# bare.net
KiCad netlist of a schematic drawn in EAGLE
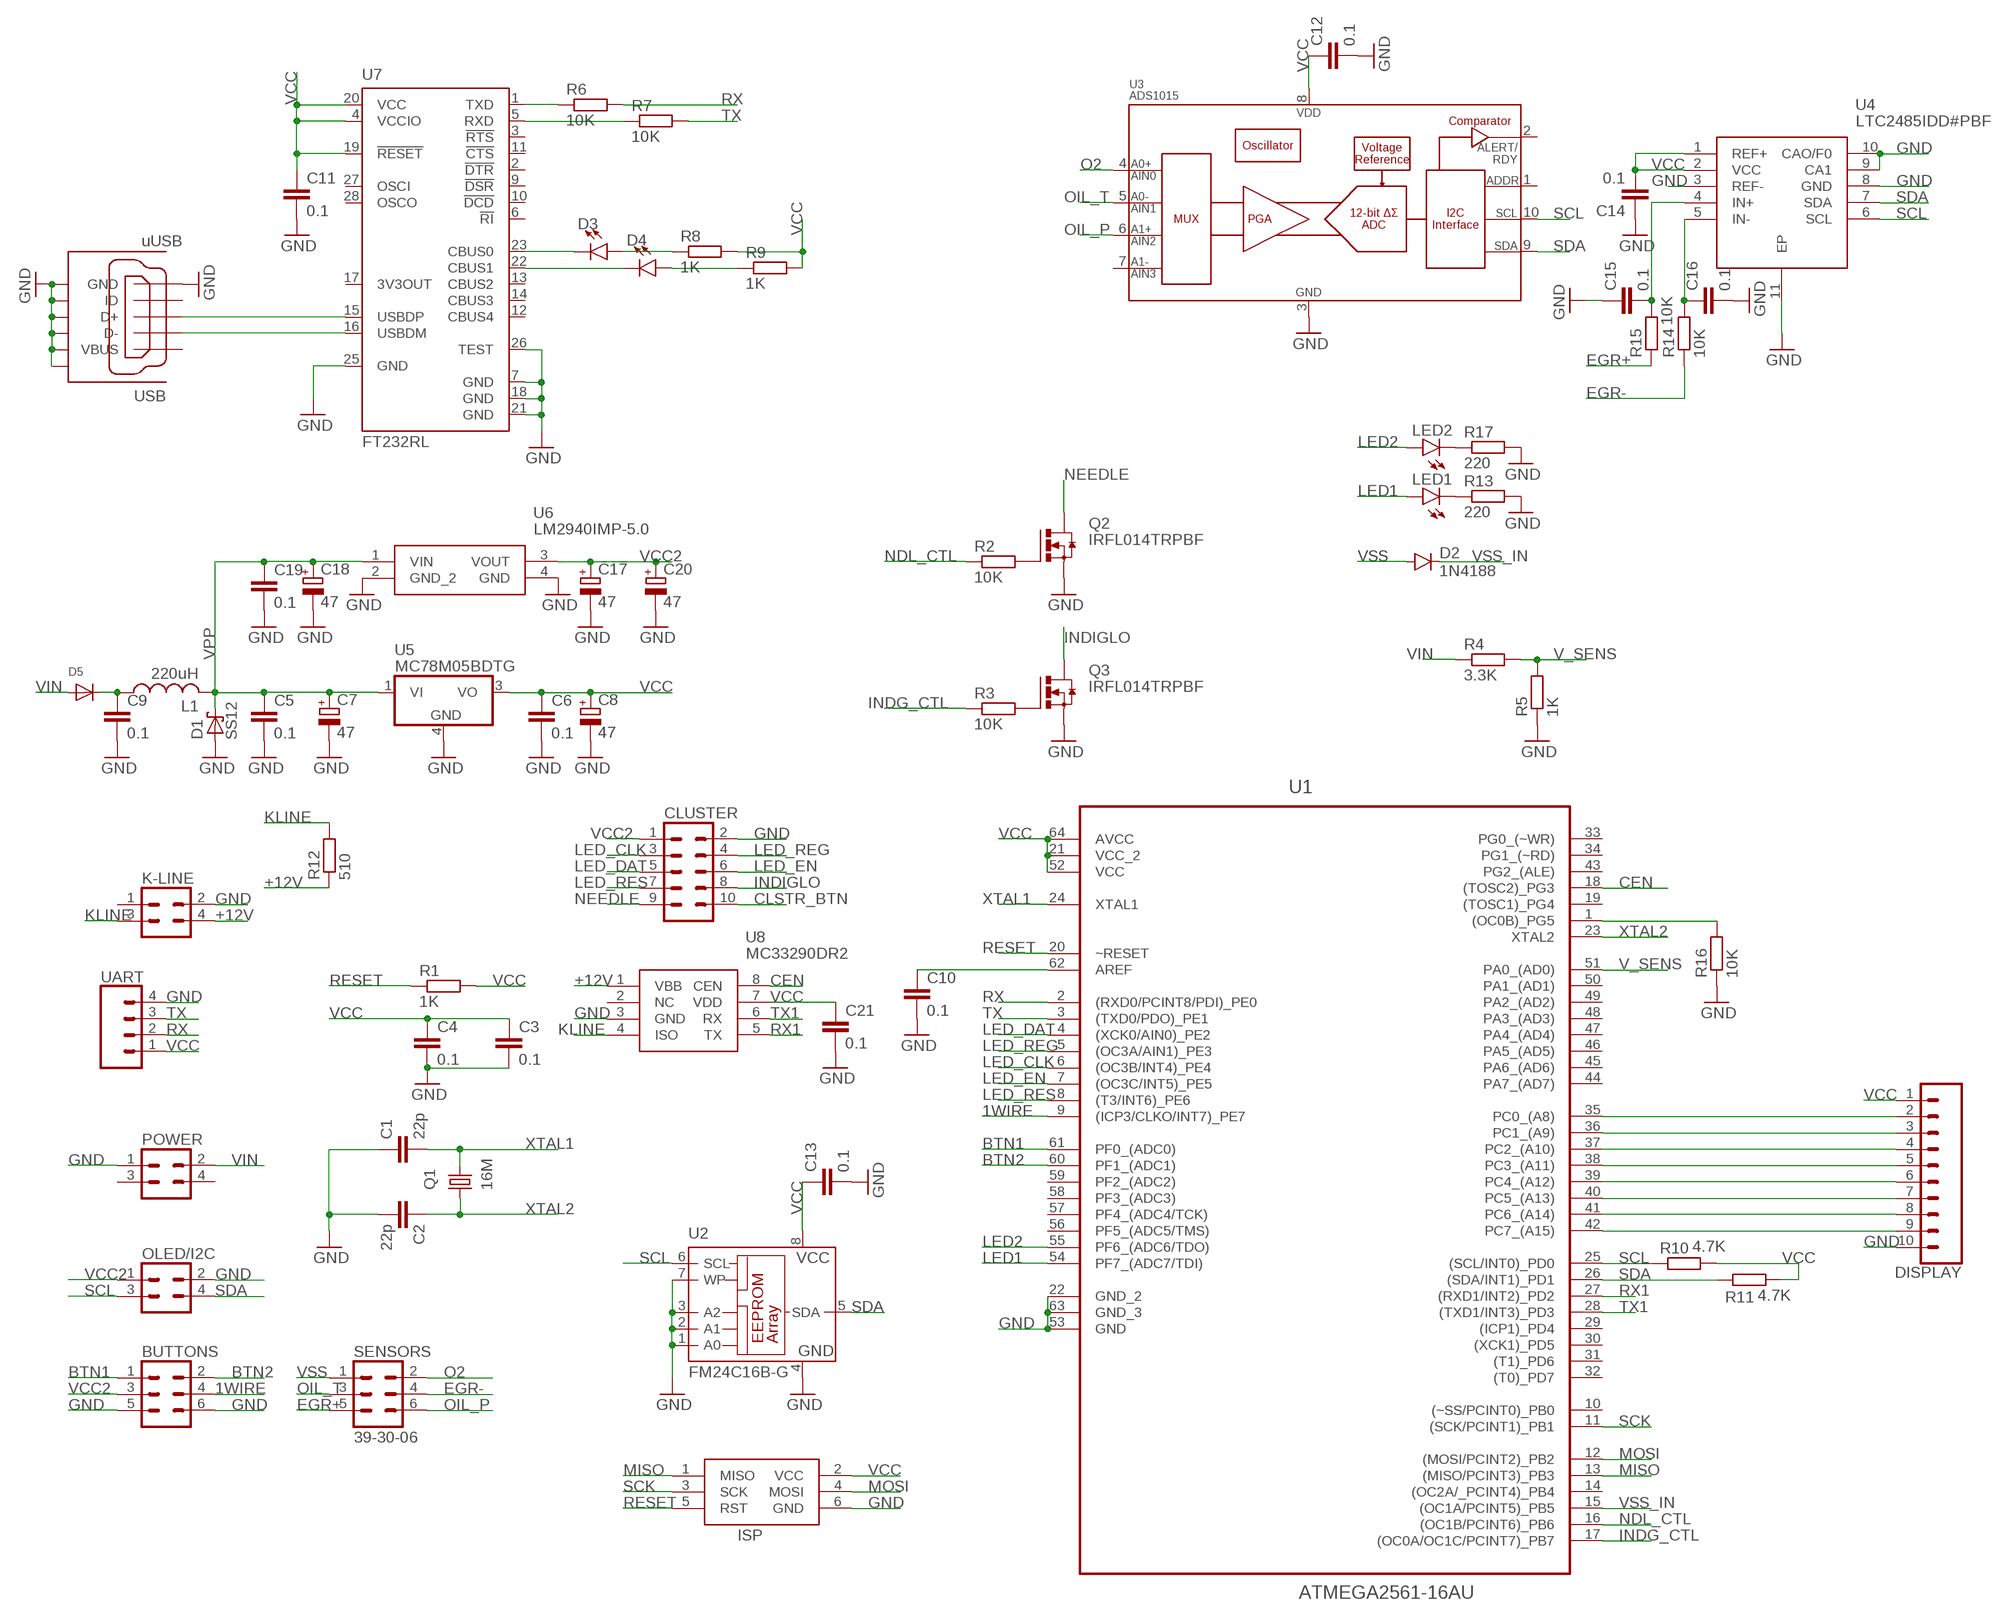
[diagram p0: schematic, sheet 1]

(export (version "E")
  (design (tool "Eeschema 10.0.6"))
  (components
    (comp (ref "BUTTONS")
      (value "39-30-06")
      (footprint "eagle-import:39-30-_06_")
      (libsource (lib "eagle-import") (part "39-30-?06?"))
    )
    (comp (ref "C1")
      (value "22p")
      (footprint "eagle-import:C0603K")
      (libsource (lib "eagle-import") (part "C-EUC0603K"))
    )
    (comp (ref "C2")
      (value "22p")
      (footprint "eagle-import:C0603K")
      (libsource (lib "eagle-import") (part "C-EUC0603K"))
    )
    (comp (ref "C3")
      (value "0.1")
      (footprint "eagle-import:C0603K")
      (libsource (lib "eagle-import") (part "C-EUC0603K"))
    )
    (comp (ref "C4")
      (value "0.1")
      (footprint "eagle-import:C0603K")
      (libsource (lib "eagle-import") (part "C-EUC0603K"))
    )
    (comp (ref "C5")
      (value "0.1")
      (footprint "eagle-import:C0805K")
      (libsource (lib "eagle-import") (part "C-EUC0805K"))
    )
    (comp (ref "C6")
      (value "0.1")
      (footprint "eagle-import:C0805K")
      (libsource (lib "eagle-import") (part "C-EUC0805K"))
    )
    (comp (ref "C7")
      (value "47")
      (footprint "eagle-import:SMC_C")
      (libsource (lib "eagle-import") (part "CPOL-EUSMCC"))
    )
    (comp (ref "C8")
      (value "47")
      (footprint "eagle-import:SMC_C")
      (libsource (lib "eagle-import") (part "CPOL-EUSMCC"))
    )
    (comp (ref "C9")
      (value "0.1")
      (footprint "eagle-import:C0805K")
      (libsource (lib "eagle-import") (part "C-EUC0805K"))
    )
    (comp (ref "C10")
      (value "0.1")
      (footprint "eagle-import:C0603K")
      (libsource (lib "eagle-import") (part "C-EUC0603K"))
    )
    (comp (ref "C11")
      (value "0.1")
      (footprint "eagle-import:C0603K")
      (libsource (lib "eagle-import") (part "C-EUC0603K"))
    )
    (comp (ref "C12")
      (value "0.1")
      (footprint "eagle-import:C0805K")
      (libsource (lib "eagle-import") (part "C-EUC0805K"))
    )
    (comp (ref "C13")
      (value "0.1")
      (footprint "eagle-import:C0603K")
      (libsource (lib "eagle-import") (part "C-EUC0603K"))
    )
    (comp (ref "C14")
      (value "0.1")
      (footprint "eagle-import:C0603K")
      (libsource (lib "eagle-import") (part "C-EUC0603K"))
    )
    (comp (ref "C15")
      (value "0.1")
      (footprint "eagle-import:C0603K")
      (libsource (lib "eagle-import") (part "C-EUC0603K"))
    )
    (comp (ref "C16")
      (value "0.1")
      (footprint "eagle-import:C0603K")
      (libsource (lib "eagle-import") (part "C-EUC0603K"))
    )
    (comp (ref "C17")
      (value "47")
      (footprint "eagle-import:SMC_C")
      (libsource (lib "eagle-import") (part "CPOL-EUSMCC"))
    )
    (comp (ref "C18")
      (value "47")
      (footprint "eagle-import:SMC_C")
      (libsource (lib "eagle-import") (part "CPOL-EUSMCC"))
    )
    (comp (ref "C19")
      (value "0.1")
      (footprint "eagle-import:C0805K")
      (libsource (lib "eagle-import") (part "C-EUC0805K"))
    )
    (comp (ref "C20")
      (value "47")
      (footprint "eagle-import:SMC_C")
      (libsource (lib "eagle-import") (part "CPOL-EUSMCC"))
    )
    (comp (ref "C21")
      (value "0.1")
      (footprint "eagle-import:C0603K")
      (libsource (lib "eagle-import") (part "C-EUC0603K"))
    )
    (comp (ref "CLUSTER")
      (value "39-30-10")
      (footprint "eagle-import:39-30-_10_")
      (libsource (lib "eagle-import") (part "39-30-?10?"))
    )
    (comp (ref "D1")
      (value "SS12")
      (footprint "eagle-import:SOD80C")
      (libsource (lib "eagle-import") (part "BAS85"))
    )
    (comp (ref "D2")
      (value "1N4188")
      (footprint "eagle-import:SOD-323")
      (libsource (lib "eagle-import") (part "DIODESOD"))
    )
    (comp (ref "D3")
      (value "GREEN")
      (footprint "eagle-import:LED-0603")
      (libsource (lib "eagle-import") (part "LED-GREEN0603"))
    )
    (comp (ref "D4")
      (value "RED")
      (footprint "eagle-import:LED-0603")
      (libsource (lib "eagle-import") (part "LED-RED0603"))
    )
    (comp (ref "D5")
      (value "DIODESMA")
      (footprint "eagle-import:SMADIODE")
      (libsource (lib "eagle-import") (part "adafruit_420_DIODESMA"))
    )
    (comp (ref "DISPLAY")
      (value "CONN_10\"")
      (footprint "eagle-import:1X10")
      (libsource (lib "eagle-import") (part "CONN_10{dblquote}"))
    )
    (comp (ref "ISP")
      (value "AVRISP-6")
      (footprint "eagle-import:AVRISP")
      (libsource (lib "eagle-import") (part "AVRISP-6"))
    )
    (comp (ref "K-LINE")
      (value "39-30-04")
      (footprint "eagle-import:39-30-_04_")
      (libsource (lib "eagle-import") (part "39-30-?04?"))
    )
    (comp (ref "L1")
      (value "220uH")
      (footprint "eagle-import:PIS2816")
      (libsource (lib "eagle-import") (part "L-USPIS2816"))
    )
    (comp (ref "LED1")
      (value "LEDCHIP-LED0805")
      (footprint "eagle-import:CHIP-LED0805")
      (libsource (lib "eagle-import") (part "LEDCHIP-LED0805"))
    )
    (comp (ref "LED2")
      (value "LEDCHIP-LED0805")
      (footprint "eagle-import:CHIP-LED0805")
      (libsource (lib "eagle-import") (part "LEDCHIP-LED0805"))
    )
    (comp (ref "OLED/I2C")
      (value "39-30-04")
      (footprint "eagle-import:39-30-_04_")
      (libsource (lib "eagle-import") (part "39-30-?04?"))
    )
    (comp (ref "POWER")
      (value "39-30-04")
      (footprint "eagle-import:39-30-_04_")
      (libsource (lib "eagle-import") (part "39-30-?04?"))
    )
    (comp (ref "Q1")
      (value "16M")
      (footprint "eagle-import:3.2X2.5_KX-7")
      (libsource (lib "eagle-import") (part "KX-7"))
    )
    (comp (ref "Q2")
      (value "IRFL014TRPBF")
      (footprint "eagle-import:SOT223")
      (libsource (lib "eagle-import") (part "N-HEXFET-2D_?-SOT232"))
    )
    (comp (ref "Q3")
      (value "IRFL014TRPBF")
      (footprint "eagle-import:SOT223")
      (libsource (lib "eagle-import") (part "N-HEXFET-2D_?-SOT232"))
    )
    (comp (ref "R1")
      (value "1K")
      (footprint "eagle-import:R0603")
      (libsource (lib "eagle-import") (part "R-EU_R0603"))
    )
    (comp (ref "R2")
      (value "10K")
      (footprint "eagle-import:R0603")
      (libsource (lib "eagle-import") (part "R-EU_R0603"))
    )
    (comp (ref "R3")
      (value "10K")
      (footprint "eagle-import:R0603")
      (libsource (lib "eagle-import") (part "R-EU_R0603"))
    )
    (comp (ref "R4")
      (value "3.3K")
      (footprint "eagle-import:R0603")
      (libsource (lib "eagle-import") (part "R-EU_R0603"))
    )
    (comp (ref "R5")
      (value "1K")
      (footprint "eagle-import:R0603")
      (libsource (lib "eagle-import") (part "R-EU_R0603"))
    )
    (comp (ref "R6")
      (value "10K")
      (footprint "eagle-import:R0603")
      (libsource (lib "eagle-import") (part "R-EU_R0603"))
    )
    (comp (ref "R7")
      (value "10K")
      (footprint "eagle-import:R0603")
      (libsource (lib "eagle-import") (part "R-EU_R0603"))
    )
    (comp (ref "R8")
      (value "1K")
      (footprint "eagle-import:R0603")
      (libsource (lib "eagle-import") (part "R-EU_R0603"))
    )
    (comp (ref "R9")
      (value "1K")
      (footprint "eagle-import:R0603")
      (libsource (lib "eagle-import") (part "R-EU_R0603"))
    )
    (comp (ref "R10")
      (value "4.7K")
      (footprint "eagle-import:R0603")
      (libsource (lib "eagle-import") (part "R-EU_R0603"))
    )
    (comp (ref "R11")
      (value "4.7K")
      (footprint "eagle-import:R0603")
      (libsource (lib "eagle-import") (part "R-EU_R0603"))
    )
    (comp (ref "R12")
      (value "510")
      (footprint "eagle-import:R0603")
      (libsource (lib "eagle-import") (part "R-EU_R0603"))
    )
    (comp (ref "R13")
      (value "220")
      (footprint "eagle-import:R0603")
      (libsource (lib "eagle-import") (part "R-EU_R0603"))
    )
    (comp (ref "R14")
      (value "10K")
      (footprint "eagle-import:R0603")
      (libsource (lib "eagle-import") (part "R-EU_R0603"))
    )
    (comp (ref "R15")
      (value "10K")
      (footprint "eagle-import:R0603")
      (libsource (lib "eagle-import") (part "R-EU_R0603"))
    )
    (comp (ref "R16")
      (value "10K")
      (footprint "eagle-import:R0603")
      (libsource (lib "eagle-import") (part "R-EU_R0603"))
    )
    (comp (ref "R17")
      (value "220")
      (footprint "eagle-import:R0603")
      (libsource (lib "eagle-import") (part "R-EU_R0603"))
    )
    (comp (ref "SENSORS")
      (value "39-30-06")
      (footprint "eagle-import:39-30-_06_")
      (libsource (lib "eagle-import") (part "39-30-?06?"))
    )
    (comp (ref "U1")
      (value "ATMEGA2561-16AU")
      (footprint "eagle-import:QFP80P1600X1600X120-64N")
      (libsource (lib "eagle-import") (part "ATMEGA2561-16AU"))
    )
    (comp (ref "U2")
      (value "FM24C16B-G")
      (footprint "eagle-import:SO-08")
      (fields (field (name "MPN") "24AA256T-I/SM"))
      (libsource (lib "eagle-import") (part "24SNAA256"))
    )
    (comp (ref "U3")
      (value "ADS1015")
      (footprint "eagle-import:MSOP10")
      (libsource (lib "eagle-import") (part "ADS1015"))
    )
    (comp (ref "U4")
      (value "LTC2485IDD#PBF")
      (footprint "eagle-import:SON50P300X300X80-11N")
      (fields (field (name "RS_PART_NUMBER") "1580322"))
      (libsource (lib "eagle-import") (part "LTC2485IDD#PBF"))
    )
    (comp (ref "U5")
      (value "MC78M05BDTG")
      (footprint "eagle-import:DPACK_3")
      (libsource (lib "eagle-import") (part "MC78M05BDTG"))
    )
    (comp (ref "U6")
      (value "LM2940IMP-5.0")
      (footprint "eagle-import:SOT230P696X180-4N")
      (fields (field (name "MOUSER_PART_NUMBER") "926-LM2940IMP-50"))
      (libsource (lib "eagle-import") (part "LM2940IMP-5.0"))
    )
    (comp (ref "U7")
      (value "FT232RL")
      (footprint "eagle-import:SSOP28")
      (libsource (lib "eagle-import") (part "FT232RL"))
    )
    (comp (ref "U8")
      (value "MC33290DR2")
      (footprint "eagle-import:SOIC127P600X175-8N")
      (libsource (lib "eagle-import") (part "MC33290DR2"))
    )
    (comp (ref "UART")
      (value "UART")
      (footprint "eagle-import:1X04")
      (libsource (lib "eagle-import") (part "CONN_04"))
    )
    (comp (ref "USB")
      (value "uUSB")
      (footprint "eagle-import:GHI-CONNECTORS_10118192-0001LF(MICRO-USB-B-AMPHENOL-FCI)")
      (libsource (lib "eagle-import") (part "GHI-CONNECTORS_10118192-0001LF"))
    )
  )
  (nets
    (net (code "1") (name "/+12V") (class "Default")
      (node (ref "K-LINE") (pin "4") (pinfunction "4_4") (pintype "passive"))
      (node (ref "R12") (pin "1") (pinfunction "1_1") (pintype "passive"))
      (node (ref "U8") (pin "1") (pinfunction "VBB_1") (pintype "bidirectional"))
    )
    (net (code "2") (name "/1WIRE") (class "Default")
      (node (ref "BUTTONS") (pin "4") (pinfunction "4_4") (pintype "passive"))
      (node (ref "U1") (pin "9") (pinfunction "(ICP3/CLKO/INT7)_PE7_9") (pintype "bidirectional"))
    )
    (net (code "3") (name "/BTN1") (class "Default")
      (node (ref "BUTTONS") (pin "1") (pinfunction "1_1") (pintype "passive"))
      (node (ref "U1") (pin "61") (pinfunction "PF0_(ADC0)_61") (pintype "bidirectional"))
    )
    (net (code "4") (name "/BTN2") (class "Default")
      (node (ref "BUTTONS") (pin "2") (pinfunction "2_2") (pintype "passive"))
      (node (ref "U1") (pin "60") (pinfunction "PF1_(ADC1)_60") (pintype "bidirectional"))
    )
    (net (code "5") (name "/CEN") (class "Default")
      (node (ref "U1") (pin "18") (pinfunction "(TOSC2)_PG3_18") (pintype "bidirectional"))
      (node (ref "U8") (pin "8") (pinfunction "CEN_8") (pintype "bidirectional"))
    )
    (net (code "6") (name "/CLSTR_BTN") (class "Default")
      (node (ref "CLUSTER") (pin "10") (pinfunction "10_10") (pintype "passive"))
      (node (ref "R16") (pin "2") (pinfunction "2_2") (pintype "passive"))
      (node (ref "U1") (pin "1") (pinfunction "(OC0B)_PG5_1") (pintype "bidirectional"))
    )
    (net (code "7") (name "/EGR+") (class "Default")
      (node (ref "R15") (pin "1") (pinfunction "1_1") (pintype "passive"))
      (node (ref "SENSORS") (pin "5") (pinfunction "5_5") (pintype "passive"))
    )
    (net (code "8") (name "/EGR-") (class "Default")
      (node (ref "R14") (pin "1") (pinfunction "1_1") (pintype "passive"))
      (node (ref "SENSORS") (pin "4") (pinfunction "4_4") (pintype "passive"))
    )
    (net (code "9") (name "/INDG_CTL") (class "Default")
      (node (ref "R3") (pin "1") (pinfunction "1_1") (pintype "passive"))
      (node (ref "U1") (pin "17") (pinfunction "(OC0A/OC1C/PCINT7)_PB7_17") (pintype "bidirectional"))
    )
    (net (code "10") (name "/INDIGLO") (class "Default")
      (node (ref "CLUSTER") (pin "8") (pinfunction "8_8") (pintype "passive"))
      (node (ref "Q3") (pin "2") (pinfunction "D_2") (pintype "passive"))
      (node (ref "Q3") (pin "4") (pinfunction "D_4") (pintype "passive"))
    )
    (net (code "11") (name "/KLINE") (class "Default")
      (node (ref "K-LINE") (pin "3") (pinfunction "3_3") (pintype "passive"))
      (node (ref "R12") (pin "2") (pinfunction "2_2") (pintype "passive"))
      (node (ref "U8") (pin "4") (pinfunction "ISO_4") (pintype "bidirectional"))
    )
    (net (code "12") (name "/LED1") (class "Default")
      (node (ref "LED1") (pin "A") (pinfunction "A_A") (pintype "passive"))
      (node (ref "U1") (pin "54") (pinfunction "PF7_(ADC7/TDI)_54") (pintype "bidirectional"))
    )
    (net (code "13") (name "/LED2") (class "Default")
      (node (ref "LED2") (pin "A") (pinfunction "A_A") (pintype "passive"))
      (node (ref "U1") (pin "55") (pinfunction "PF6_(ADC6/TDO)_55") (pintype "bidirectional"))
    )
    (net (code "14") (name "/LED_CLK") (class "Default")
      (node (ref "CLUSTER") (pin "3") (pinfunction "3_3") (pintype "passive"))
      (node (ref "U1") (pin "6") (pinfunction "(OC3B/INT4)_PE4_6") (pintype "bidirectional"))
    )
    (net (code "15") (name "/LED_DAT") (class "Default")
      (node (ref "CLUSTER") (pin "5") (pinfunction "5_5") (pintype "passive"))
      (node (ref "U1") (pin "4") (pinfunction "(XCK0/AIN0)_PE2_4") (pintype "bidirectional"))
    )
    (net (code "16") (name "/LED_EN") (class "Default")
      (node (ref "CLUSTER") (pin "6") (pinfunction "6_6") (pintype "passive"))
      (node (ref "U1") (pin "7") (pinfunction "(OC3C/INT5)_PE5_7") (pintype "bidirectional"))
    )
    (net (code "17") (name "/LED_REG") (class "Default")
      (node (ref "CLUSTER") (pin "4") (pinfunction "4_4") (pintype "passive"))
      (node (ref "U1") (pin "5") (pinfunction "(OC3A/AIN1)_PE3_5") (pintype "bidirectional"))
    )
    (net (code "18") (name "/LED_RES") (class "Default")
      (node (ref "CLUSTER") (pin "7") (pinfunction "7_7") (pintype "passive"))
      (node (ref "U1") (pin "8") (pinfunction "(T3/INT6)_PE6_8") (pintype "bidirectional"))
    )
    (net (code "19") (name "/MISO") (class "Default")
      (node (ref "ISP") (pin "1") (pinfunction "MISO_1") (pintype "input"))
      (node (ref "U1") (pin "13") (pinfunction "(MISO/PCINT3)_PB3_13") (pintype "bidirectional"))
    )
    (net (code "20") (name "/MOSI") (class "Default")
      (node (ref "ISP") (pin "4") (pinfunction "MOSI_4") (pintype "output"))
      (node (ref "U1") (pin "12") (pinfunction "(MOSI/PCINT2)_PB2_12") (pintype "bidirectional"))
    )
    (net (code "21") (name "/NDL_CTL") (class "Default")
      (node (ref "R2") (pin "1") (pinfunction "1_1") (pintype "passive"))
      (node (ref "U1") (pin "16") (pinfunction "(OC1B/PCINT6)_PB6_16") (pintype "bidirectional"))
    )
    (net (code "22") (name "/NEEDLE") (class "Default")
      (node (ref "CLUSTER") (pin "9") (pinfunction "9_9") (pintype "passive"))
      (node (ref "Q2") (pin "2") (pinfunction "D_2") (pintype "passive"))
      (node (ref "Q2") (pin "4") (pinfunction "D_4") (pintype "passive"))
    )
    (net (code "23") (name "/O2") (class "Default")
      (node (ref "SENSORS") (pin "2") (pinfunction "2_2") (pintype "passive"))
      (node (ref "U3") (pin "4") (pinfunction "AIN0_4") (pintype "bidirectional"))
    )
    (net (code "24") (name "/OIL_P") (class "Default")
      (node (ref "SENSORS") (pin "6") (pinfunction "6_6") (pintype "passive"))
      (node (ref "U3") (pin "6") (pinfunction "AIN2_6") (pintype "bidirectional"))
    )
    (net (code "25") (name "/OIL_T") (class "Default")
      (node (ref "SENSORS") (pin "3") (pinfunction "3_3") (pintype "passive"))
      (node (ref "U3") (pin "5") (pinfunction "AIN1_5") (pintype "bidirectional"))
    )
    (net (code "26") (name "/RESET") (class "Default")
      (node (ref "ISP") (pin "5") (pinfunction "RST_5") (pintype "output"))
      (node (ref "R1") (pin "1") (pinfunction "1_1") (pintype "passive"))
      (node (ref "U1") (pin "20") (pinfunction "~{RESET}_20") (pintype "input"))
    )
    (net (code "27") (name "/RX") (class "Default")
      (node (ref "R6") (pin "2") (pinfunction "2_2") (pintype "passive"))
      (node (ref "U1") (pin "2") (pinfunction "(RXD0/PCINT8/PDI)_PE0_2") (pintype "bidirectional"))
      (node (ref "UART") (pin "2") (pinfunction "2_2") (pintype "passive"))
    )
    (net (code "28") (name "/RX1") (class "Default")
      (node (ref "U1") (pin "27") (pinfunction "(RXD1/INT2)_PD2_27") (pintype "bidirectional"))
      (node (ref "U8") (pin "5") (pinfunction "TX_5") (pintype "bidirectional"))
    )
    (net (code "29") (name "/SCK") (class "Default")
      (node (ref "ISP") (pin "3") (pinfunction "SCK_3") (pintype "output"))
      (node (ref "U1") (pin "11") (pinfunction "(SCK/PCINT1)_PB1_11") (pintype "bidirectional"))
    )
    (net (code "30") (name "/SCL") (class "Default")
      (node (ref "OLED/I2C") (pin "3") (pinfunction "3_3") (pintype "passive"))
      (node (ref "R10") (pin "1") (pinfunction "1_1") (pintype "passive"))
      (node (ref "U1") (pin "25") (pinfunction "(SCL/INT0)_PD0_25") (pintype "bidirectional"))
      (node (ref "U2") (pin "6") (pinfunction "SCL_6") (pintype "input"))
      (node (ref "U3") (pin "10") (pinfunction "SCL_10") (pintype "bidirectional"))
      (node (ref "U4") (pin "6") (pinfunction "SCL_6") (pintype "bidirectional"))
    )
    (net (code "31") (name "/SDA") (class "Default")
      (node (ref "OLED/I2C") (pin "4") (pinfunction "4_4") (pintype "passive"))
      (node (ref "R11") (pin "1") (pinfunction "1_1") (pintype "passive"))
      (node (ref "U1") (pin "26") (pinfunction "(SDA/INT1)_PD1_26") (pintype "bidirectional"))
      (node (ref "U2") (pin "5") (pinfunction "SDA_5") (pintype "bidirectional"))
      (node (ref "U3") (pin "9") (pinfunction "SDA_9") (pintype "bidirectional"))
      (node (ref "U4") (pin "7") (pinfunction "SDA_7") (pintype "bidirectional"))
    )
    (net (code "32") (name "/TX") (class "Default")
      (node (ref "R7") (pin "2") (pinfunction "2_2") (pintype "passive"))
      (node (ref "U1") (pin "3") (pinfunction "(TXD0/PDO)_PE1_3") (pintype "bidirectional"))
      (node (ref "UART") (pin "3") (pinfunction "3_3") (pintype "passive"))
    )
    (net (code "33") (name "/TX1") (class "Default")
      (node (ref "U1") (pin "28") (pinfunction "(TXD1/INT3)_PD3_28") (pintype "bidirectional"))
      (node (ref "U8") (pin "6") (pinfunction "RX_6") (pintype "bidirectional"))
    )
    (net (code "34") (name "/VCC") (class "Default")
      (node (ref "C11") (pin "1") (pinfunction "1_1") (pintype "passive"))
      (node (ref "C12") (pin "1") (pinfunction "1_1") (pintype "passive"))
      (node (ref "C13") (pin "1") (pinfunction "1_1") (pintype "passive"))
      (node (ref "C14") (pin "2") (pinfunction "2_2") (pintype "passive"))
      (node (ref "C21") (pin "1") (pinfunction "1_1") (pintype "passive"))
      (node (ref "C3") (pin "1") (pinfunction "1_1") (pintype "passive"))
      (node (ref "C4") (pin "1") (pinfunction "1_1") (pintype "passive"))
      (node (ref "C6") (pin "1") (pinfunction "1_1") (pintype "passive"))
      (node (ref "C8") (pin "+") (pinfunction "+_+") (pintype "passive"))
      (node (ref "DISPLAY") (pin "1") (pinfunction "1_1") (pintype "passive"))
      (node (ref "ISP") (pin "2") (pinfunction "VCC_2") (pintype "power_in"))
      (node (ref "R1") (pin "2") (pinfunction "2_2") (pintype "passive"))
      (node (ref "R10") (pin "2") (pinfunction "2_2") (pintype "passive"))
      (node (ref "R11") (pin "2") (pinfunction "2_2") (pintype "passive"))
      (node (ref "R8") (pin "2") (pinfunction "2_2") (pintype "passive"))
      (node (ref "R9") (pin "2") (pinfunction "2_2") (pintype "passive"))
      (node (ref "U1") (pin "21") (pinfunction "VCC_2_21") (pintype "power_in"))
      (node (ref "U1") (pin "52") (pinfunction "VCC_52") (pintype "power_in"))
      (node (ref "U1") (pin "64") (pinfunction "AVCC_64") (pintype "power_in"))
      (node (ref "U2") (pin "8") (pinfunction "VCC_8") (pintype "power_in"))
      (node (ref "U3") (pin "8") (pinfunction "VDD_8") (pintype "bidirectional"))
      (node (ref "U4") (pin "1") (pinfunction "REF+_1") (pintype "bidirectional"))
      (node (ref "U4") (pin "2") (pinfunction "VCC_2") (pintype "bidirectional"))
      (node (ref "U5") (pin "3") (pinfunction "VO_3") (pintype "passive"))
      (node (ref "U7") (pin "19") (pinfunction "~{RESET}_19") (pintype "input"))
      (node (ref "U7") (pin "20") (pinfunction "VCC_20") (pintype "power_in"))
      (node (ref "U7") (pin "4") (pinfunction "VCCIO_4") (pintype "power_in"))
      (node (ref "U8") (pin "7") (pinfunction "VDD_7") (pintype "bidirectional"))
      (node (ref "UART") (pin "1") (pinfunction "1_1") (pintype "passive"))
    )
    (net (code "35") (name "/VCC2") (class "Default")
      (node (ref "BUTTONS") (pin "3") (pinfunction "3_3") (pintype "passive"))
      (node (ref "C17") (pin "+") (pinfunction "+_+") (pintype "passive"))
      (node (ref "C20") (pin "+") (pinfunction "+_+") (pintype "passive"))
      (node (ref "CLUSTER") (pin "1") (pinfunction "1_1") (pintype "passive"))
      (node (ref "OLED/I2C") (pin "1") (pinfunction "1_1") (pintype "passive"))
      (node (ref "U6") (pin "3") (pinfunction "VOUT_3") (pintype "bidirectional"))
    )
    (net (code "36") (name "/VIN") (class "Default")
      (node (ref "D5") (pin "A") (pinfunction "A_A") (pintype "passive"))
      (node (ref "POWER") (pin "2") (pinfunction "2_2") (pintype "passive"))
      (node (ref "R4") (pin "1") (pinfunction "1_1") (pintype "passive"))
    )
    (net (code "37") (name "/VPP") (class "Default")
      (node (ref "C18") (pin "+") (pinfunction "+_+") (pintype "passive"))
      (node (ref "C19") (pin "1") (pinfunction "1_1") (pintype "passive"))
      (node (ref "C5") (pin "1") (pinfunction "1_1") (pintype "passive"))
      (node (ref "C7") (pin "+") (pinfunction "+_+") (pintype "passive"))
      (node (ref "D1") (pin "1") (pinfunction "K_1") (pintype "passive"))
      (node (ref "L1") (pin "2") (pinfunction "2_2") (pintype "passive"))
      (node (ref "U5") (pin "1") (pinfunction "VI_1") (pintype "input"))
      (node (ref "U6") (pin "1") (pinfunction "VIN_1") (pintype "bidirectional"))
    )
    (net (code "38") (name "/VSS") (class "Default")
      (node (ref "D2") (pin "A") (pinfunction "A_A") (pintype "passive"))
      (node (ref "SENSORS") (pin "1") (pinfunction "1_1") (pintype "passive"))
    )
    (net (code "39") (name "/VSS_IN") (class "Default")
      (node (ref "D2") (pin "C") (pinfunction "C_C") (pintype "passive"))
      (node (ref "U1") (pin "15") (pinfunction "(OC1A/PCINT5)_PB5_15") (pintype "bidirectional"))
    )
    (net (code "40") (name "/V_SENS") (class "Default")
      (node (ref "R4") (pin "2") (pinfunction "2_2") (pintype "passive"))
      (node (ref "R5") (pin "2") (pinfunction "2_2") (pintype "passive"))
      (node (ref "U1") (pin "51") (pinfunction "PA0_(AD0)_51") (pintype "bidirectional"))
    )
    (net (code "41") (name "/XTAL1") (class "Default")
      (node (ref "C1") (pin "2") (pinfunction "2_2") (pintype "passive"))
      (node (ref "Q1") (pin "3") (pinfunction "2_3") (pintype "passive"))
      (node (ref "U1") (pin "24") (pinfunction "XTAL1_24") (pintype "input"))
    )
    (net (code "42") (name "/XTAL2") (class "Default")
      (node (ref "C2") (pin "1") (pinfunction "1_1") (pintype "passive"))
      (node (ref "Q1") (pin "1") (pinfunction "1_1") (pintype "passive"))
      (node (ref "U1") (pin "23") (pinfunction "XTAL2_23") (pintype "output"))
    )
    (net (code "43") (name "GND") (class "Default")
      (node (ref "BUTTONS") (pin "5") (pinfunction "5_5") (pintype "passive"))
      (node (ref "BUTTONS") (pin "6") (pinfunction "6_6") (pintype "passive"))
      (node (ref "C1") (pin "1") (pinfunction "1_1") (pintype "passive"))
      (node (ref "C10") (pin "2") (pinfunction "2_2") (pintype "passive"))
      (node (ref "C11") (pin "2") (pinfunction "2_2") (pintype "passive"))
      (node (ref "C12") (pin "2") (pinfunction "2_2") (pintype "passive"))
      (node (ref "C13") (pin "2") (pinfunction "2_2") (pintype "passive"))
      (node (ref "C14") (pin "1") (pinfunction "1_1") (pintype "passive"))
      (node (ref "C15") (pin "1") (pinfunction "1_1") (pintype "passive"))
      (node (ref "C16") (pin "2") (pinfunction "2_2") (pintype "passive"))
      (node (ref "C17") (pin "-") (pinfunction "-_-") (pintype "passive"))
      (node (ref "C18") (pin "-") (pinfunction "-_-") (pintype "passive"))
      (node (ref "C19") (pin "2") (pinfunction "2_2") (pintype "passive"))
      (node (ref "C2") (pin "2") (pinfunction "2_2") (pintype "passive"))
      (node (ref "C20") (pin "-") (pinfunction "-_-") (pintype "passive"))
      (node (ref "C21") (pin "2") (pinfunction "2_2") (pintype "passive"))
      (node (ref "C3") (pin "2") (pinfunction "2_2") (pintype "passive"))
      (node (ref "C4") (pin "2") (pinfunction "2_2") (pintype "passive"))
      (node (ref "C5") (pin "2") (pinfunction "2_2") (pintype "passive"))
      (node (ref "C6") (pin "2") (pinfunction "2_2") (pintype "passive"))
      (node (ref "C7") (pin "-") (pinfunction "-_-") (pintype "passive"))
      (node (ref "C8") (pin "-") (pinfunction "-_-") (pintype "passive"))
      (node (ref "C9") (pin "2") (pinfunction "2_2") (pintype "passive"))
      (node (ref "CLUSTER") (pin "2") (pinfunction "2_2") (pintype "passive"))
      (node (ref "D1") (pin "2") (pinfunction "A_2") (pintype "passive"))
      (node (ref "DISPLAY") (pin "10") (pinfunction "10_10") (pintype "passive"))
      (node (ref "ISP") (pin "6") (pinfunction "GND_6") (pintype "power_in"))
      (node (ref "K-LINE") (pin "2") (pinfunction "2_2") (pintype "passive"))
      (node (ref "OLED/I2C") (pin "2") (pinfunction "2_2") (pintype "passive"))
      (node (ref "POWER") (pin "1") (pinfunction "1_1") (pintype "passive"))
      (node (ref "Q2") (pin "3") (pinfunction "S_3") (pintype "passive"))
      (node (ref "Q3") (pin "3") (pinfunction "S_3") (pintype "passive"))
      (node (ref "R13") (pin "2") (pinfunction "2_2") (pintype "passive"))
      (node (ref "R16") (pin "1") (pinfunction "1_1") (pintype "passive"))
      (node (ref "R17") (pin "2") (pinfunction "2_2") (pintype "passive"))
      (node (ref "R5") (pin "1") (pinfunction "1_1") (pintype "passive"))
      (node (ref "U1") (pin "22") (pinfunction "GND_2_22") (pintype "passive"))
      (node (ref "U1") (pin "53") (pinfunction "GND_53") (pintype "passive"))
      (node (ref "U1") (pin "63") (pinfunction "GND_3_63") (pintype "passive"))
      (node (ref "U2") (pin "1") (pinfunction "A0_1") (pintype "input"))
      (node (ref "U2") (pin "2") (pinfunction "A1_2") (pintype "input"))
      (node (ref "U2") (pin "3") (pinfunction "A2_3") (pintype "input"))
      (node (ref "U2") (pin "4") (pinfunction "GND_4") (pintype "power_in"))
      (node (ref "U2") (pin "7") (pinfunction "WP_7") (pintype "input"))
      (node (ref "U3") (pin "3") (pinfunction "VSS_3") (pintype "bidirectional"))
      (node (ref "U4") (pin "10") (pinfunction "CAO/F0_10") (pintype "bidirectional"))
      (node (ref "U4") (pin "11") (pinfunction "EP_11") (pintype "bidirectional"))
      (node (ref "U4") (pin "3") (pinfunction "REF-_3") (pintype "bidirectional"))
      (node (ref "U4") (pin "8") (pinfunction "GND_8") (pintype "bidirectional"))
      (node (ref "U4") (pin "9") (pinfunction "CA1_9") (pintype "bidirectional"))
      (node (ref "U5") (pin "4") (pinfunction "GND_4") (pintype "passive"))
      (node (ref "U6") (pin "2") (pinfunction "GND_2_2") (pintype "bidirectional"))
      (node (ref "U6") (pin "4") (pinfunction "GND_4") (pintype "bidirectional"))
      (node (ref "U7") (pin "18") (pinfunction "GND_18") (pintype "power_in"))
      (node (ref "U7") (pin "21") (pinfunction "GND_21") (pintype "power_in"))
      (node (ref "U7") (pin "25") (pinfunction "GND_25") (pintype "power_in"))
      (node (ref "U7") (pin "26") (pinfunction "TEST_26") (pintype "input"))
      (node (ref "U7") (pin "7") (pinfunction "GND_7") (pintype "power_in"))
      (node (ref "U8") (pin "3") (pinfunction "GND_3") (pintype "bidirectional"))
      (node (ref "UART") (pin "4") (pinfunction "4_4") (pintype "passive"))
      (node (ref "USB") (pin "CGND1") (pinfunction "SGND1_CGND1") (pintype "bidirectional"))
      (node (ref "USB") (pin "CGND2") (pinfunction "SGND2_CGND2") (pintype "bidirectional"))
      (node (ref "USB") (pin "CGND3") (pinfunction "SGND3_CGND3") (pintype "bidirectional"))
      (node (ref "USB") (pin "CGND4") (pinfunction "SGND4_CGND4") (pintype "bidirectional"))
      (node (ref "USB") (pin "CGND5") (pinfunction "SGND5_CGND5") (pintype "bidirectional"))
      (node (ref "USB") (pin "CGND6") (pinfunction "SGND6_CGND6") (pintype "bidirectional"))
      (node (ref "USB") (pin "GND") (pinfunction "GND_GND") (pintype "input"))
    )
    (net (code "44") (name "Net-(C9-Pad1)") (class "Default")
      (node (ref "C9") (pin "1") (pinfunction "1_1") (pintype "passive"))
      (node (ref "D5") (pin "C") (pinfunction "C_C") (pintype "passive"))
      (node (ref "L1") (pin "1") (pinfunction "1_1") (pintype "passive"))
    )
    (net (code "45") (name "Net-(D3-PadA)") (class "Default")
      (node (ref "D3") (pin "A") (pinfunction "A_A") (pintype "passive"))
      (node (ref "R8") (pin "1") (pinfunction "1_1") (pintype "passive"))
    )
    (net (code "46") (name "Net-(D4-PadA)") (class "Default")
      (node (ref "D4") (pin "A") (pinfunction "A_A") (pintype "passive"))
      (node (ref "R9") (pin "1") (pinfunction "1_1") (pintype "passive"))
    )
    (net (code "47") (name "Net-(LED1-PadC)") (class "Default")
      (node (ref "LED1") (pin "C") (pinfunction "C_C") (pintype "passive"))
      (node (ref "R13") (pin "1") (pinfunction "1_1") (pintype "passive"))
    )
    (net (code "48") (name "Net-(LED2-PadC)") (class "Default")
      (node (ref "LED2") (pin "C") (pinfunction "C_C") (pintype "passive"))
      (node (ref "R17") (pin "1") (pinfunction "1_1") (pintype "passive"))
    )
    (net (code "49") (name "Net-(Q2-G)") (class "Default")
      (node (ref "Q2") (pin "1") (pinfunction "G_1") (pintype "passive"))
      (node (ref "R2") (pin "2") (pinfunction "2_2") (pintype "passive"))
    )
    (net (code "50") (name "Net-(Q3-G)") (class "Default")
      (node (ref "Q3") (pin "1") (pinfunction "G_1") (pintype "passive"))
      (node (ref "R3") (pin "2") (pinfunction "2_2") (pintype "passive"))
    )
    (net (code "51") (name "Net-(U1-AREF)") (class "Default")
      (node (ref "C10") (pin "1") (pinfunction "1_1") (pintype "passive"))
      (node (ref "U1") (pin "62") (pinfunction "AREF_62") (pintype "input"))
    )
    (net (code "52") (name "Net-(U1-PC0_(A8))") (class "Default")
      (node (ref "DISPLAY") (pin "2") (pinfunction "2_2") (pintype "passive"))
      (node (ref "U1") (pin "35") (pinfunction "PC0_(A8)_35") (pintype "bidirectional"))
    )
    (net (code "53") (name "Net-(U1-PC1_(A9))") (class "Default")
      (node (ref "DISPLAY") (pin "3") (pinfunction "3_3") (pintype "passive"))
      (node (ref "U1") (pin "36") (pinfunction "PC1_(A9)_36") (pintype "bidirectional"))
    )
    (net (code "54") (name "Net-(U1-PC2_(A10))") (class "Default")
      (node (ref "DISPLAY") (pin "4") (pinfunction "4_4") (pintype "passive"))
      (node (ref "U1") (pin "37") (pinfunction "PC2_(A10)_37") (pintype "bidirectional"))
    )
    (net (code "55") (name "Net-(U1-PC3_(A11))") (class "Default")
      (node (ref "DISPLAY") (pin "5") (pinfunction "5_5") (pintype "passive"))
      (node (ref "U1") (pin "38") (pinfunction "PC3_(A11)_38") (pintype "bidirectional"))
    )
    (net (code "56") (name "Net-(U1-PC4_(A12))") (class "Default")
      (node (ref "DISPLAY") (pin "6") (pinfunction "6_6") (pintype "passive"))
      (node (ref "U1") (pin "39") (pinfunction "PC4_(A12)_39") (pintype "bidirectional"))
    )
    (net (code "57") (name "Net-(U1-PC5_(A13))") (class "Default")
      (node (ref "DISPLAY") (pin "7") (pinfunction "7_7") (pintype "passive"))
      (node (ref "U1") (pin "40") (pinfunction "PC5_(A13)_40") (pintype "bidirectional"))
    )
    (net (code "58") (name "Net-(U1-PC6_(A14))") (class "Default")
      (node (ref "DISPLAY") (pin "8") (pinfunction "8_8") (pintype "passive"))
      (node (ref "U1") (pin "41") (pinfunction "PC6_(A14)_41") (pintype "bidirectional"))
    )
    (net (code "59") (name "Net-(U1-PC7_(A15))") (class "Default")
      (node (ref "DISPLAY") (pin "9") (pinfunction "9_9") (pintype "passive"))
      (node (ref "U1") (pin "42") (pinfunction "PC7_(A15)_42") (pintype "bidirectional"))
    )
    (net (code "60") (name "Net-(U4-IN+)") (class "Default")
      (node (ref "C15") (pin "2") (pinfunction "2_2") (pintype "passive"))
      (node (ref "R15") (pin "2") (pinfunction "2_2") (pintype "passive"))
      (node (ref "U4") (pin "4") (pinfunction "IN+_4") (pintype "bidirectional"))
    )
    (net (code "61") (name "Net-(U4-IN-)") (class "Default")
      (node (ref "C16") (pin "1") (pinfunction "1_1") (pintype "passive"))
      (node (ref "R14") (pin "2") (pinfunction "2_2") (pintype "passive"))
      (node (ref "U4") (pin "5") (pinfunction "IN-_5") (pintype "bidirectional"))
    )
    (net (code "62") (name "Net-(U7-CBUS0)") (class "Default")
      (node (ref "D3") (pin "C") (pinfunction "C_C") (pintype "passive"))
      (node (ref "U7") (pin "23") (pinfunction "CBUS0_23") (pintype "bidirectional"))
    )
    (net (code "63") (name "Net-(U7-CBUS1)") (class "Default")
      (node (ref "D4") (pin "C") (pinfunction "C_C") (pintype "passive"))
      (node (ref "U7") (pin "22") (pinfunction "CBUS1_22") (pintype "bidirectional"))
    )
    (net (code "64") (name "Net-(U7-RXD)") (class "Default")
      (node (ref "R7") (pin "1") (pinfunction "1_1") (pintype "passive"))
      (node (ref "U7") (pin "5") (pinfunction "RXD_5") (pintype "input"))
    )
    (net (code "65") (name "Net-(U7-TXD)") (class "Default")
      (node (ref "R6") (pin "1") (pinfunction "1_1") (pintype "passive"))
      (node (ref "U7") (pin "1") (pinfunction "TXD_1") (pintype "output"))
    )
    (net (code "66") (name "Net-(U7-USBDM)") (class "Default")
      (node (ref "U7") (pin "16") (pinfunction "USBDM_16") (pintype "bidirectional"))
      (node (ref "USB") (pin "D-") (pinfunction "D-_D-") (pintype "input"))
    )
    (net (code "67") (name "Net-(U7-USBDP)") (class "Default")
      (node (ref "U7") (pin "15") (pinfunction "USBDP_15") (pintype "bidirectional"))
      (node (ref "USB") (pin "D+") (pinfunction "D+_D+") (pintype "input"))
    )
    (net (code "68") (name "unconnected-(K-LINE-Pad1)") (class "Default")
      (node (ref "K-LINE") (pin "1") (pinfunction "1_1") (pintype "passive"))
    )
    (net (code "69") (name "unconnected-(POWER-Pad3)") (class "Default")
      (node (ref "POWER") (pin "3") (pinfunction "3_3") (pintype "passive"))
    )
    (net (code "70") (name "unconnected-(POWER-Pad4)") (class "Default")
      (node (ref "POWER") (pin "4") (pinfunction "4_4") (pintype "passive"))
    )
    (net (code "71") (name "unconnected-(U1-(ICP1)_PD4-Pad29)") (class "Default")
      (node (ref "U1") (pin "29") (pinfunction "(ICP1)_PD4_29") (pintype "bidirectional"))
    )
    (net (code "72") (name "unconnected-(U1-(OC2A{slash}_PCINT4)_PB4-Pad14)") (class "Default")
      (node (ref "U1") (pin "14") (pinfunction "(OC2A/_PCINT4)_PB4_14") (pintype "bidirectional"))
    )
    (net (code "73") (name "unconnected-(U1-(T0)_PD7-Pad32)") (class "Default")
      (node (ref "U1") (pin "32") (pinfunction "(T0)_PD7_32") (pintype "bidirectional"))
    )
    (net (code "74") (name "unconnected-(U1-(T1)_PD6-Pad31)") (class "Default")
      (node (ref "U1") (pin "31") (pinfunction "(T1)_PD6_31") (pintype "bidirectional"))
    )
    (net (code "75") (name "unconnected-(U1-(TOSC1)_PG4-Pad19)") (class "Default")
      (node (ref "U1") (pin "19") (pinfunction "(TOSC1)_PG4_19") (pintype "bidirectional"))
    )
    (net (code "76") (name "unconnected-(U1-(XCK1)_PD5-Pad30)") (class "Default")
      (node (ref "U1") (pin "30") (pinfunction "(XCK1)_PD5_30") (pintype "bidirectional"))
    )
    (net (code "77") (name "unconnected-(U1-(~{SS{slash}PCINT0})_PB0-Pad10)") (class "Default")
      (node (ref "U1") (pin "10") (pinfunction "(~{SS/PCINT0})_PB0_10") (pintype "bidirectional"))
    )
    (net (code "78") (name "unconnected-(U1-PA1_(AD1)-Pad50)") (class "Default")
      (node (ref "U1") (pin "50") (pinfunction "PA1_(AD1)_50") (pintype "bidirectional"))
    )
    (net (code "79") (name "unconnected-(U1-PA2_(AD2)-Pad49)") (class "Default")
      (node (ref "U1") (pin "49") (pinfunction "PA2_(AD2)_49") (pintype "bidirectional"))
    )
    (net (code "80") (name "unconnected-(U1-PA3_(AD3)-Pad48)") (class "Default")
      (node (ref "U1") (pin "48") (pinfunction "PA3_(AD3)_48") (pintype "bidirectional"))
    )
    (net (code "81") (name "unconnected-(U1-PA4_(AD4)-Pad47)") (class "Default")
      (node (ref "U1") (pin "47") (pinfunction "PA4_(AD4)_47") (pintype "bidirectional"))
    )
    (net (code "82") (name "unconnected-(U1-PA5_(AD5)-Pad46)") (class "Default")
      (node (ref "U1") (pin "46") (pinfunction "PA5_(AD5)_46") (pintype "bidirectional"))
    )
    (net (code "83") (name "unconnected-(U1-PA6_(AD6)-Pad45)") (class "Default")
      (node (ref "U1") (pin "45") (pinfunction "PA6_(AD6)_45") (pintype "bidirectional"))
    )
    (net (code "84") (name "unconnected-(U1-PA7_(AD7)-Pad44)") (class "Default")
      (node (ref "U1") (pin "44") (pinfunction "PA7_(AD7)_44") (pintype "bidirectional"))
    )
    (net (code "85") (name "unconnected-(U1-PF2_(ADC2)-Pad59)") (class "Default")
      (node (ref "U1") (pin "59") (pinfunction "PF2_(ADC2)_59") (pintype "bidirectional"))
    )
    (net (code "86") (name "unconnected-(U1-PF3_(ADC3)-Pad58)") (class "Default")
      (node (ref "U1") (pin "58") (pinfunction "PF3_(ADC3)_58") (pintype "bidirectional"))
    )
    (net (code "87") (name "unconnected-(U1-PF4_(ADC4{slash}TCK)-Pad57)") (class "Default")
      (node (ref "U1") (pin "57") (pinfunction "PF4_(ADC4/TCK)_57") (pintype "bidirectional"))
    )
    (net (code "88") (name "unconnected-(U1-PF5_(ADC5{slash}TMS)-Pad56)") (class "Default")
      (node (ref "U1") (pin "56") (pinfunction "PF5_(ADC5/TMS)_56") (pintype "bidirectional"))
    )
    (net (code "89") (name "unconnected-(U1-PG0_(~{WR})-Pad33)") (class "Default")
      (node (ref "U1") (pin "33") (pinfunction "PG0_(~{WR})_33") (pintype "bidirectional"))
    )
    (net (code "90") (name "unconnected-(U1-PG1_(~{RD})-Pad34)") (class "Default")
      (node (ref "U1") (pin "34") (pinfunction "PG1_(~{RD})_34") (pintype "bidirectional"))
    )
    (net (code "91") (name "unconnected-(U1-PG2_(ALE)-Pad43)") (class "Default")
      (node (ref "U1") (pin "43") (pinfunction "PG2_(ALE)_43") (pintype "bidirectional"))
    )
    (net (code "92") (name "unconnected-(U3-ADDR-Pad1)") (class "Default")
      (node (ref "U3") (pin "1") (pinfunction "ADDR_1") (pintype "bidirectional"))
    )
    (net (code "93") (name "unconnected-(U3-AIN3-Pad7)") (class "Default")
      (node (ref "U3") (pin "7") (pinfunction "AIN3_7") (pintype "bidirectional"))
    )
    (net (code "94") (name "unconnected-(U3-ALERT{slash}RDY-Pad2)") (class "Default")
      (node (ref "U3") (pin "2") (pinfunction "ALERT/RDY_2") (pintype "bidirectional"))
    )
    (net (code "95") (name "unconnected-(U7-3V3OUT-Pad17)") (class "Default")
      (node (ref "U7") (pin "17") (pinfunction "3V3OUT_17") (pintype "output"))
    )
    (net (code "96") (name "unconnected-(U7-CBUS2-Pad13)") (class "Default")
      (node (ref "U7") (pin "13") (pinfunction "CBUS2_13") (pintype "bidirectional"))
    )
    (net (code "97") (name "unconnected-(U7-CBUS3-Pad14)") (class "Default")
      (node (ref "U7") (pin "14") (pinfunction "CBUS3_14") (pintype "bidirectional"))
    )
    (net (code "98") (name "unconnected-(U7-CBUS4-Pad12)") (class "Default")
      (node (ref "U7") (pin "12") (pinfunction "CBUS4_12") (pintype "bidirectional"))
    )
    (net (code "99") (name "unconnected-(U7-OSCI-Pad27)") (class "Default")
      (node (ref "U7") (pin "27") (pinfunction "OSCI_27") (pintype "input"))
    )
    (net (code "100") (name "unconnected-(U7-OSCO-Pad28)") (class "Default")
      (node (ref "U7") (pin "28") (pinfunction "OSCO_28") (pintype "output"))
    )
    (net (code "101") (name "unconnected-(U7-~{CTS}-Pad11)") (class "Default")
      (node (ref "U7") (pin "11") (pinfunction "~{CTS}_11") (pintype "input"))
    )
    (net (code "102") (name "unconnected-(U7-~{DCD}-Pad10)") (class "Default")
      (node (ref "U7") (pin "10") (pinfunction "~{DCD}_10") (pintype "input"))
    )
    (net (code "103") (name "unconnected-(U7-~{DSR}-Pad9)") (class "Default")
      (node (ref "U7") (pin "9") (pinfunction "~{DSR}_9") (pintype "input"))
    )
    (net (code "104") (name "unconnected-(U7-~{DTR}-Pad2)") (class "Default")
      (node (ref "U7") (pin "2") (pinfunction "~{DTR}_2") (pintype "output"))
    )
    (net (code "105") (name "unconnected-(U7-~{RI}-Pad6)") (class "Default")
      (node (ref "U7") (pin "6") (pinfunction "~{RI}_6") (pintype "input"))
    )
    (net (code "106") (name "unconnected-(U7-~{RTS}-Pad3)") (class "Default")
      (node (ref "U7") (pin "3") (pinfunction "~{RTS}_3") (pintype "output"))
    )
    (net (code "107") (name "unconnected-(U8-NC-Pad2)") (class "Default")
      (node (ref "U8") (pin "2") (pinfunction "NC_2") (pintype "no_connect"))
    )
    (net (code "108") (name "unconnected-(USB-PadID)") (class "Default")
      (node (ref "USB") (pin "ID") (pinfunction "ID_ID") (pintype "input"))
    )
    (net (code "109") (name "unconnected-(USB-PadVBUS)") (class "Default")
      (node (ref "USB") (pin "VBUS") (pinfunction "VBUS_VBUS") (pintype "input"))
    )
  )
)
